# AiSWCA_pcb.net
KiCad netlist of a schematic drawn in EAGLE
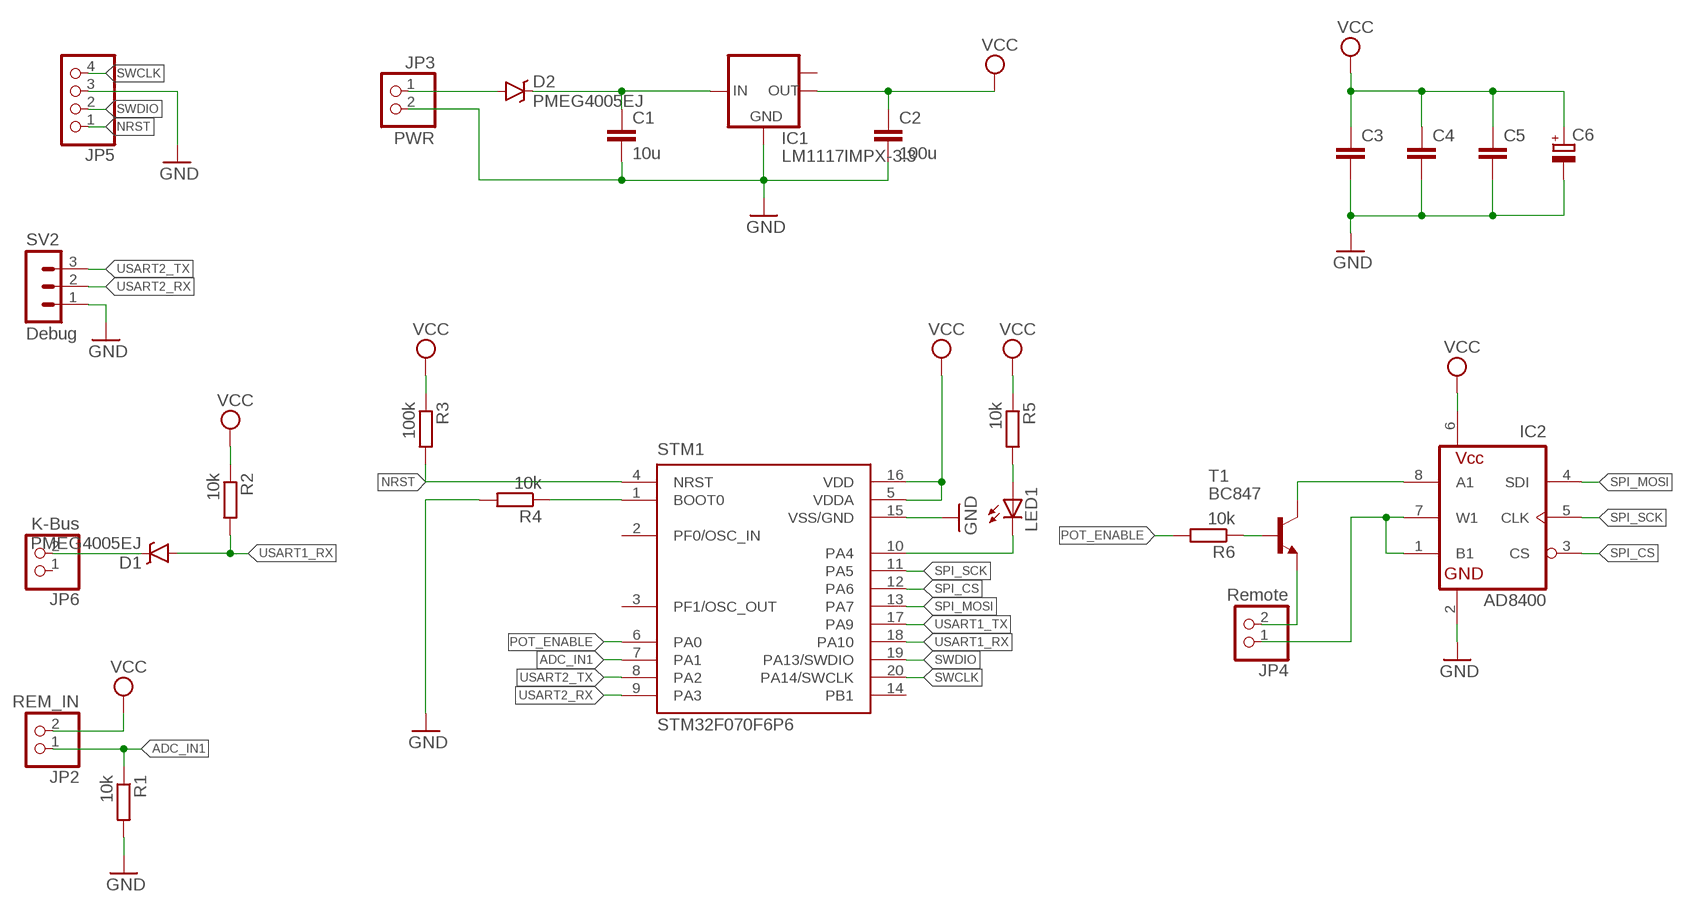
[diagram p0: schematic, sheet 1]

(export (version "E")
  (design (tool "Eeschema 10.0.6"))
  (components
    (comp (ref "C1")
      (value "10u")
      (footprint "eagle-import:C0805")
      (libsource (lib "eagle-import") (part "C-EUC0805"))
    )
    (comp (ref "C2")
      (value "100u")
      (footprint "eagle-import:C0805")
      (libsource (lib "eagle-import") (part "C-EUC0805"))
    )
    (comp (ref "C3")
      (value "C-EUC0805")
      (footprint "eagle-import:C0805")
      (libsource (lib "eagle-import") (part "C-EUC0805"))
    )
    (comp (ref "C4")
      (value "C-EUC0805")
      (footprint "eagle-import:C0805")
      (libsource (lib "eagle-import") (part "C-EUC0805"))
    )
    (comp (ref "C5")
      (value "C-EUC0805")
      (footprint "eagle-import:C0805")
      (libsource (lib "eagle-import") (part "C-EUC0805"))
    )
    (comp (ref "C6")
      (value "CPOL-EUB/3528-21W")
      (footprint "eagle-import:B_3528-21W")
      (libsource (lib "eagle-import") (part "CPOL-EUB/3528-21W"))
    )
    (comp (ref "D1")
      (value "PMEG4005EJ")
      (footprint "eagle-import:SOD-323")
      (libsource (lib "eagle-import") (part "DIODE-SCHOTTKY-PMEG4005EJ"))
    )
    (comp (ref "D2")
      (value "PMEG4005EJ")
      (footprint "eagle-import:SOD-323")
      (libsource (lib "eagle-import") (part "DIODE-SCHOTTKY-PMEG4005EJ"))
    )
    (comp (ref "IC1")
      (value "LM1117IMPX-3.3")
      (footprint "eagle-import:SOT223")
      (libsource (lib "eagle-import") (part "LM1117IMPX-3.3"))
    )
    (comp (ref "IC2")
      (value "AD8400R")
      (footprint "eagle-import:SO8")
      (libsource (lib "eagle-import") (part "AD8400R"))
    )
    (comp (ref "JP2")
      (value "REM_IN")
      (footprint "eagle-import:1X02_90")
      (libsource (lib "eagle-import") (part "PINHD-1X2/90"))
    )
    (comp (ref "JP3")
      (value "PWR")
      (footprint "eagle-import:1X02_90")
      (libsource (lib "eagle-import") (part "PINHD-1X2/90"))
    )
    (comp (ref "JP4")
      (value "Remote")
      (footprint "eagle-import:1X02_90")
      (libsource (lib "eagle-import") (part "PINHD-1X2/90"))
    )
    (comp (ref "JP5")
      (value "PINHD-1X4/90")
      (footprint "eagle-import:1X04_90")
      (libsource (lib "eagle-import") (part "PINHD-1X4/90"))
    )
    (comp (ref "JP6")
      (value "K-Bus")
      (footprint "eagle-import:1X02_90")
      (libsource (lib "eagle-import") (part "PINHD-1X2/90"))
    )
    (comp (ref "LED1")
      (value "LEDCHIP-LED0805")
      (footprint "eagle-import:CHIP-LED0805")
      (libsource (lib "eagle-import") (part "LEDCHIP-LED0805"))
    )
    (comp (ref "R1")
      (value "10k")
      (footprint "eagle-import:R0805")
      (libsource (lib "eagle-import") (part "R-EU_R0805"))
    )
    (comp (ref "R2")
      (value "10k")
      (footprint "eagle-import:R0805")
      (libsource (lib "eagle-import") (part "R-EU_R0805"))
    )
    (comp (ref "R3")
      (value "100k")
      (footprint "eagle-import:R0805")
      (libsource (lib "eagle-import") (part "R-EU_R0805"))
    )
    (comp (ref "R4")
      (value "10k")
      (footprint "eagle-import:R0805")
      (libsource (lib "eagle-import") (part "R-EU_R0805"))
    )
    (comp (ref "R5")
      (value "10k")
      (footprint "eagle-import:R0805")
      (libsource (lib "eagle-import") (part "R-EU_R0805"))
    )
    (comp (ref "R6")
      (value "10k")
      (footprint "eagle-import:R0805")
      (libsource (lib "eagle-import") (part "R-EU_R0805"))
    )
    (comp (ref "STM1")
      (value "STM32F070F6P6")
      (footprint "eagle-import:TSSOP20")
      (libsource (lib "eagle-import") (part "STM32F030F4P6V1"))
    )
    (comp (ref "SV2")
      (value "Debug")
      (footprint "eagle-import:MA03-1")
      (libsource (lib "eagle-import") (part "MA03-1"))
    )
    (comp (ref "T1")
      (value "BC847")
      (footprint "eagle-import:SOT23")
      (libsource (lib "eagle-import") (part "BC847"))
    )
  )
  (nets
    (net (code "1") (name "ADC_IN1") (class "Default")
      (node (ref "JP2") (pin "1") (pinfunction "1_1") (pintype "passive"))
      (node (ref "R1") (pin "1") (pinfunction "1_1") (pintype "passive"))
      (node (ref "STM1") (pin "7") (pinfunction "PA1_7") (pintype "bidirectional"))
    )
    (net (code "2") (name "GND") (class "Default")
      (node (ref "C1") (pin "2") (pinfunction "2_2") (pintype "passive"))
      (node (ref "C2") (pin "2") (pinfunction "2_2") (pintype "passive"))
      (node (ref "C3") (pin "2") (pinfunction "2_2") (pintype "passive"))
      (node (ref "C4") (pin "2") (pinfunction "2_2") (pintype "passive"))
      (node (ref "C5") (pin "2") (pinfunction "2_2") (pintype "passive"))
      (node (ref "C6") (pin "-") (pinfunction "-_-") (pintype "passive"))
      (node (ref "IC1") (pin "1") (pinfunction "GND_1") (pintype "input"))
      (node (ref "IC2") (pin "2") (pinfunction "GND_2") (pintype "power_in"))
      (node (ref "JP3") (pin "2") (pinfunction "2_2") (pintype "passive"))
      (node (ref "JP5") (pin "3") (pinfunction "3_3") (pintype "passive"))
      (node (ref "R1") (pin "2") (pinfunction "2_2") (pintype "passive"))
      (node (ref "R4") (pin "2") (pinfunction "2_2") (pintype "passive"))
      (node (ref "STM1") (pin "15") (pinfunction "VSS/GND_15") (pintype "power_in"))
      (node (ref "SV2") (pin "1") (pinfunction "1_1") (pintype "passive"))
    )
    (net (code "3") (name "NRST") (class "Default")
      (node (ref "JP5") (pin "1") (pinfunction "1_1") (pintype "passive"))
      (node (ref "R3") (pin "2") (pinfunction "2_2") (pintype "passive"))
      (node (ref "STM1") (pin "4") (pinfunction "NRST_4") (pintype "bidirectional"))
    )
    (net (code "4") (name "Net-(D1-PadC)") (class "Default")
      (node (ref "D1") (pin "C") (pinfunction "C_C") (pintype "passive"))
      (node (ref "JP6") (pin "2") (pinfunction "2_2") (pintype "passive"))
    )
    (net (code "5") (name "Net-(D2-PadA)") (class "Default")
      (node (ref "D2") (pin "A") (pinfunction "A_A") (pintype "passive"))
      (node (ref "JP3") (pin "1") (pinfunction "1_1") (pintype "passive"))
    )
    (net (code "6") (name "Net-(IC1-IN)") (class "Default")
      (node (ref "C1") (pin "1") (pinfunction "1_1") (pintype "passive"))
      (node (ref "D2") (pin "C") (pinfunction "C_C") (pintype "passive"))
      (node (ref "IC1") (pin "3") (pinfunction "IN_3") (pintype "input"))
    )
    (net (code "7") (name "Net-(IC2-A1)") (class "Default")
      (node (ref "IC2") (pin "8") (pinfunction "A1_8") (pintype "passive"))
      (node (ref "T1") (pin "3") (pinfunction "C_3") (pintype "passive"))
    )
    (net (code "8") (name "Net-(IC2-B1)") (class "Default")
      (node (ref "IC2") (pin "1") (pinfunction "B1_1") (pintype "passive"))
      (node (ref "IC2") (pin "7") (pinfunction "W1_7") (pintype "passive"))
      (node (ref "JP4") (pin "1") (pinfunction "1_1") (pintype "passive"))
    )
    (net (code "9") (name "Net-(LED1-PadA)") (class "Default")
      (node (ref "LED1") (pin "A") (pinfunction "A_A") (pintype "passive"))
      (node (ref "R5") (pin "2") (pinfunction "2_2") (pintype "passive"))
    )
    (net (code "10") (name "Net-(STM1-BOOT0)") (class "Default")
      (node (ref "R4") (pin "1") (pinfunction "1_1") (pintype "passive"))
      (node (ref "STM1") (pin "1") (pinfunction "BOOT0_1") (pintype "bidirectional"))
    )
    (net (code "11") (name "Net-(STM1-PA4)") (class "Default")
      (node (ref "LED1") (pin "C") (pinfunction "C_C") (pintype "passive"))
      (node (ref "STM1") (pin "10") (pinfunction "PA4_10") (pintype "bidirectional"))
    )
    (net (code "12") (name "Net-(T1-B)") (class "Default")
      (node (ref "R6") (pin "1") (pinfunction "1_1") (pintype "passive"))
      (node (ref "T1") (pin "1") (pinfunction "B_1") (pintype "passive"))
    )
    (net (code "13") (name "Net-(T1-E)") (class "Default")
      (node (ref "JP4") (pin "2") (pinfunction "2_2") (pintype "passive"))
      (node (ref "T1") (pin "2") (pinfunction "E_2") (pintype "passive"))
    )
    (net (code "14") (name "POT_ENABLE") (class "Default")
      (node (ref "R6") (pin "2") (pinfunction "2_2") (pintype "passive"))
      (node (ref "STM1") (pin "6") (pinfunction "PA0_6") (pintype "bidirectional"))
    )
    (net (code "15") (name "SPI_CS") (class "Default")
      (node (ref "IC2") (pin "3") (pinfunction "CS_3") (pintype "input"))
      (node (ref "STM1") (pin "12") (pinfunction "PA6_12") (pintype "bidirectional"))
    )
    (net (code "16") (name "SPI_MOSI") (class "Default")
      (node (ref "IC2") (pin "4") (pinfunction "SDI_4") (pintype "input"))
      (node (ref "STM1") (pin "13") (pinfunction "PA7_13") (pintype "bidirectional"))
    )
    (net (code "17") (name "SPI_SCK") (class "Default")
      (node (ref "IC2") (pin "5") (pinfunction "CLK_5") (pintype "input"))
      (node (ref "STM1") (pin "11") (pinfunction "PA5_11") (pintype "bidirectional"))
    )
    (net (code "18") (name "SWCLK") (class "Default")
      (node (ref "JP5") (pin "4") (pinfunction "4_4") (pintype "passive"))
      (node (ref "STM1") (pin "20") (pinfunction "PA14/SWCLK_20") (pintype "bidirectional"))
    )
    (net (code "19") (name "SWDIO") (class "Default")
      (node (ref "JP5") (pin "2") (pinfunction "2_2") (pintype "passive"))
      (node (ref "STM1") (pin "19") (pinfunction "PA13/SWDIO_19") (pintype "bidirectional"))
    )
    (net (code "20") (name "USART1_RX") (class "Default")
      (node (ref "D1") (pin "A") (pinfunction "A_A") (pintype "passive"))
      (node (ref "R2") (pin "2") (pinfunction "2_2") (pintype "passive"))
      (node (ref "STM1") (pin "18") (pinfunction "PA10_18") (pintype "bidirectional"))
    )
    (net (code "21") (name "USART1_TX") (class "Default")
      (node (ref "STM1") (pin "17") (pinfunction "PA9_17") (pintype "bidirectional"))
    )
    (net (code "22") (name "USART2_RX") (class "Default")
      (node (ref "STM1") (pin "9") (pinfunction "PA3_9") (pintype "bidirectional"))
      (node (ref "SV2") (pin "2") (pinfunction "2_2") (pintype "passive"))
    )
    (net (code "23") (name "USART2_TX") (class "Default")
      (node (ref "STM1") (pin "8") (pinfunction "PA2_8") (pintype "bidirectional"))
      (node (ref "SV2") (pin "3") (pinfunction "3_3") (pintype "passive"))
    )
    (net (code "24") (name "VCC") (class "Default")
      (node (ref "C2") (pin "1") (pinfunction "1_1") (pintype "passive"))
      (node (ref "C3") (pin "1") (pinfunction "1_1") (pintype "passive"))
      (node (ref "C4") (pin "1") (pinfunction "1_1") (pintype "passive"))
      (node (ref "C5") (pin "1") (pinfunction "1_1") (pintype "passive"))
      (node (ref "C6") (pin "+") (pinfunction "+_+") (pintype "passive"))
      (node (ref "IC1") (pin "2") (pinfunction "OUT_2") (pintype "passive"))
      (node (ref "IC2") (pin "6") (pinfunction "VDD_6") (pintype "power_in"))
      (node (ref "JP2") (pin "2") (pinfunction "2_2") (pintype "passive"))
      (node (ref "R2") (pin "1") (pinfunction "1_1") (pintype "passive"))
      (node (ref "R3") (pin "1") (pinfunction "1_1") (pintype "passive"))
      (node (ref "R5") (pin "1") (pinfunction "1_1") (pintype "passive"))
      (node (ref "STM1") (pin "16") (pinfunction "VDD_16") (pintype "power_in"))
      (node (ref "STM1") (pin "5") (pinfunction "VDDA_5") (pintype "power_in"))
    )
    (net (code "25") (name "unconnected-(IC1-OUT1-PadTAB)") (class "Default")
      (node (ref "IC1") (pin "TAB") (pinfunction "OUT1_TAB") (pintype "passive"))
    )
    (net (code "26") (name "unconnected-(JP6-Pad1)") (class "Default")
      (node (ref "JP6") (pin "1") (pinfunction "1_1") (pintype "passive"))
    )
    (net (code "27") (name "unconnected-(STM1-PB1-Pad14)") (class "Default")
      (node (ref "STM1") (pin "14") (pinfunction "PB1_14") (pintype "bidirectional"))
    )
    (net (code "28") (name "unconnected-(STM1-PF0{slash}OSC_IN-Pad2)") (class "Default")
      (node (ref "STM1") (pin "2") (pinfunction "PF0/OSC_IN_2") (pintype "bidirectional"))
    )
    (net (code "29") (name "unconnected-(STM1-PF1{slash}OSC_OUT-Pad3)") (class "Default")
      (node (ref "STM1") (pin "3") (pinfunction "PF1/OSC_OUT_3") (pintype "bidirectional"))
    )
  )
)
